# Motorsystem.net
KiCad netlist of a schematic drawn in EAGLE
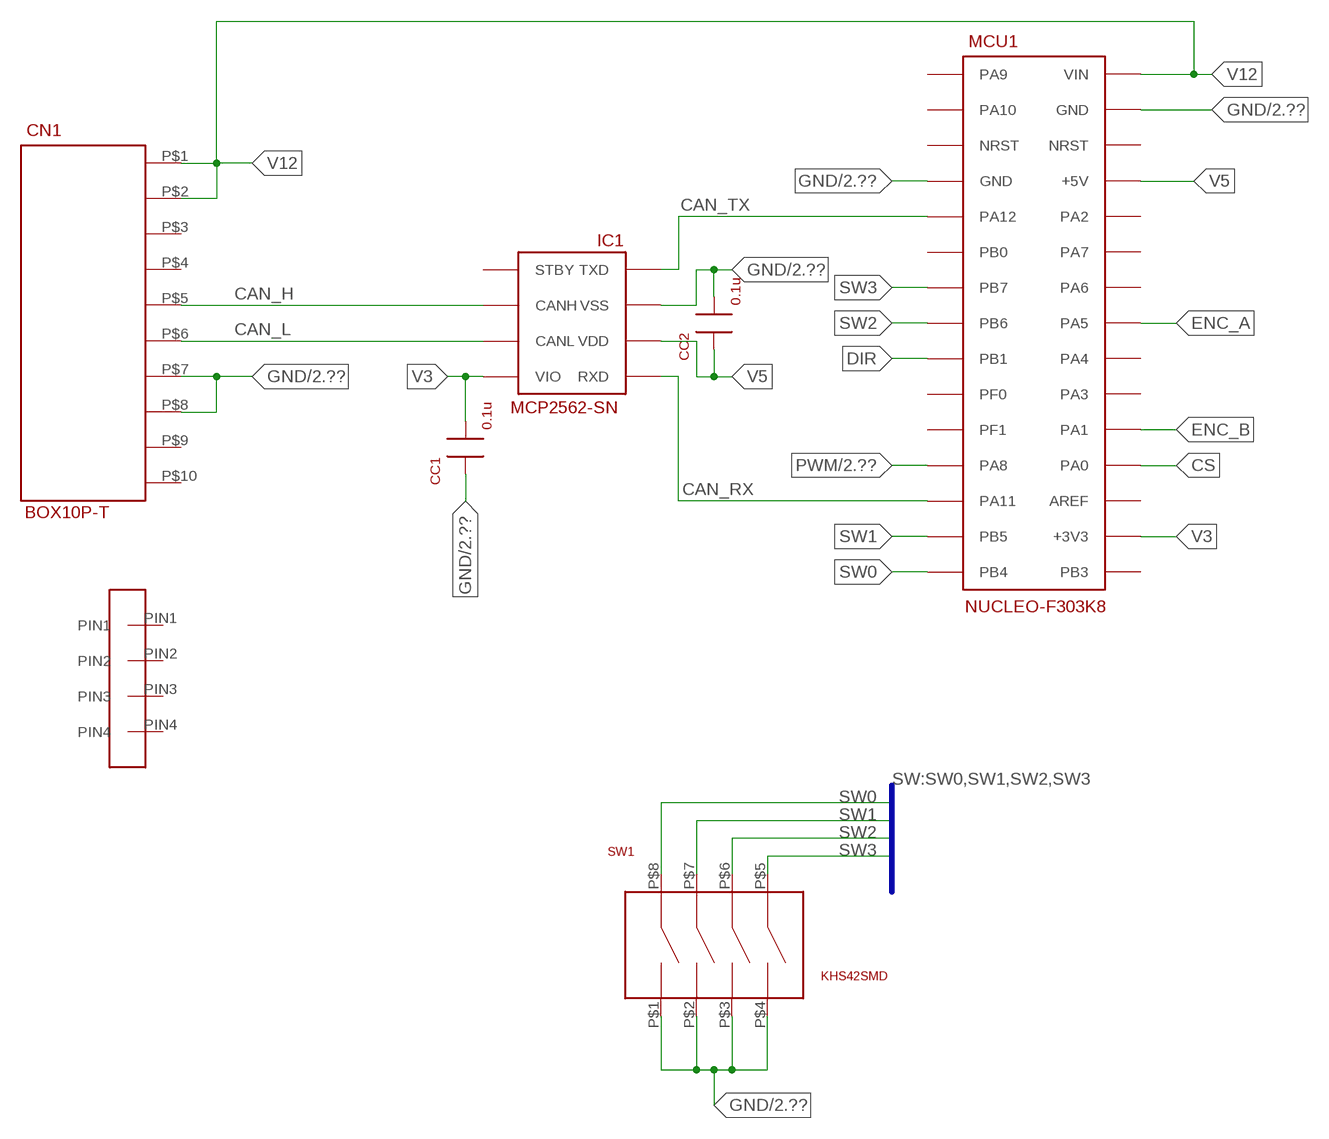
[diagram p0: schematic, sheet 1]
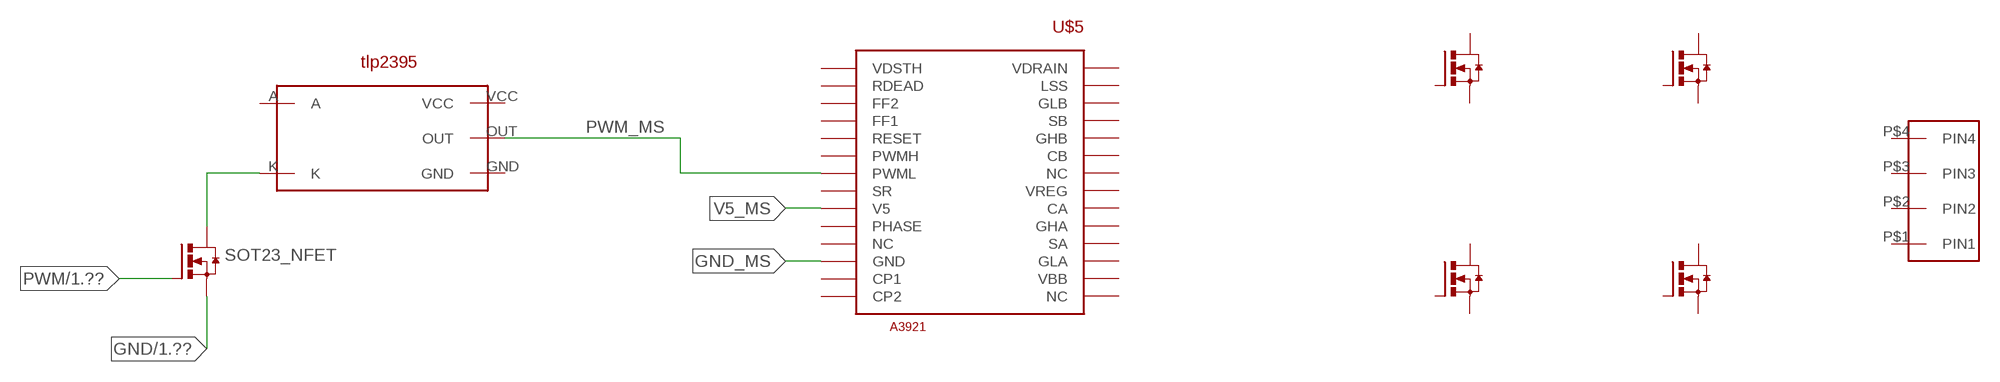
[diagram p1: schematic, sheet 2]

(export (version "E")
  (design (tool "Eeschema 10.0.6"))
  (components
    (comp (ref "CC1")
      (value "0.1u")
      (footprint "eagle-import:C1608")
      (libsource (lib "eagle-import") (part "MLCC1608"))
    )
    (comp (ref "CC2")
      (value "0.1u")
      (footprint "eagle-import:C1608")
      (libsource (lib "eagle-import") (part "MLCC1608"))
    )
    (comp (ref "CN1")
      (value "BOX10P-T")
      (footprint "eagle-import:BOX10P-T")
      (libsource (lib "eagle-import") (part "BOX10P-T"))
    )
    (comp (ref "IC1")
      (value "MCP2562-SN")
      (footprint "eagle-import:SOIC8")
      (libsource (lib "eagle-import") (part "MCP2562-SN"))
    )
    (comp (ref "MCU1")
      (value "NUCLEO-F303K8")
      (footprint "eagle-import:NUCLEO-NANO")
      (libsource (lib "eagle-import") (part "NUCLEO-F303K8"))
    )
    (comp (ref "SW1")
      (value "KHS42SMD")
      (footprint "eagle-import:KHS42")
      (libsource (lib "eagle-import") (part "KHS42SMD"))
    )
    (comp (ref "U$3")
      (value "DF1B_L_4P")
      (footprint "eagle-import:DF1B_L_4P")
      (libsource (lib "eagle-import") (part "DF1B_L_4P"))
    )
    (comp (ref "U$1")
      (value "TLP2395")
      (footprint "eagle-import:TLP2395")
      (libsource (lib "eagle-import") (part "TLP2395"))
    )
    (comp (ref "U$2")
      (value "SOT23_NFET")
      (footprint "eagle-import:SOT23_NFET")
      (libsource (lib "eagle-import") (part "SOT23_NFET"))
    )
    (comp (ref "U$4")
      (value "NP52N06SLG")
      (footprint "eagle-import:NP52N06SLG")
      (libsource (lib "eagle-import") (part "NP52N06SLG"))
    )
    (comp (ref "U$5")
      (value "A3921")
      (footprint "eagle-import:A3921")
      (libsource (lib "eagle-import") (part "A3921"))
    )
    (comp (ref "U$6")
      (value "NP52N06SLG")
      (footprint "eagle-import:NP52N06SLG")
      (libsource (lib "eagle-import") (part "NP52N06SLG"))
    )
    (comp (ref "U$7")
      (value "NP52N06SLG")
      (footprint "eagle-import:NP52N06SLG")
      (libsource (lib "eagle-import") (part "NP52N06SLG"))
    )
    (comp (ref "U$8")
      (value "NP52N06SLG")
      (footprint "eagle-import:NP52N06SLG")
      (libsource (lib "eagle-import") (part "NP52N06SLG"))
    )
    (comp (ref "U$9")
      (value "VL_4P")
      (footprint "eagle-import:VL_4P")
      (libsource (lib "eagle-import") (part "VL_4P"))
    )
  )
  (nets
    (net (code "3") (name "CAN_H") (class "Default")
      (node (ref "CN1") (pin "P$5") (pinfunction "P$5_P$5") (pintype "bidirectional"))
      (node (ref "IC1") (pin "P$7") (pinfunction "CANH_P$7") (pintype "bidirectional"))
    )
    (net (code "4") (name "CAN_L") (class "Default")
      (node (ref "CN1") (pin "P$6") (pinfunction "P$6_P$6") (pintype "bidirectional"))
      (node (ref "IC1") (pin "P$6") (pinfunction "CANL_P$6") (pintype "bidirectional"))
    )
    (net (code "5") (name "CAN_RX") (class "Default")
      (node (ref "IC1") (pin "P$4") (pinfunction "RXD_P$4") (pintype "bidirectional"))
      (node (ref "MCU1") (pin "P$13") (pinfunction "PA11_P$13") (pintype "bidirectional"))
    )
    (net (code "6") (name "CAN_TX") (class "Default")
      (node (ref "IC1") (pin "P$1") (pinfunction "TXD_P$1") (pintype "bidirectional"))
      (node (ref "MCU1") (pin "P$5") (pinfunction "PA12_P$5") (pintype "bidirectional"))
    )
    (net (code "7") (name "CS") (class "Default")
      (node (ref "MCU1") (pin "P$19") (pinfunction "PA0_P$19") (pintype "bidirectional"))
    )
    (net (code "8") (name "DIR") (class "Default")
      (node (ref "MCU1") (pin "P$9") (pinfunction "PB1_P$9") (pintype "bidirectional"))
    )
    (net (code "9") (name "ENC_A") (class "Default")
      (node (ref "MCU1") (pin "P$23") (pinfunction "PA5_P$23") (pintype "bidirectional"))
    )
    (net (code "10") (name "ENC_B") (class "Default")
      (node (ref "MCU1") (pin "P$20") (pinfunction "PA1_P$20") (pintype "bidirectional"))
    )
    (net (code "11") (name "GND") (class "Default")
      (node (ref "CC1") (pin "P$1") (pinfunction "P$1_P$1") (pintype "bidirectional"))
      (node (ref "CC2") (pin "P$2") (pinfunction "P$2_P$2") (pintype "bidirectional"))
      (node (ref "CN1") (pin "P$7") (pinfunction "P$7_P$7") (pintype "bidirectional"))
      (node (ref "CN1") (pin "P$8") (pinfunction "P$8_P$8") (pintype "bidirectional"))
      (node (ref "IC1") (pin "P$2") (pinfunction "VSS_P$2") (pintype "bidirectional"))
      (node (ref "MCU1") (pin "P$29") (pinfunction "GND_P$29") (pintype "bidirectional"))
      (node (ref "MCU1") (pin "P$4") (pinfunction "GND_P$4") (pintype "bidirectional"))
      (node (ref "SW1") (pin "P$1") (pinfunction "P$1_P$1") (pintype "bidirectional"))
      (node (ref "SW1") (pin "P$2") (pinfunction "P$2_P$2") (pintype "bidirectional"))
      (node (ref "SW1") (pin "P$3") (pinfunction "P$3_P$3") (pintype "bidirectional"))
      (node (ref "SW1") (pin "P$4") (pinfunction "P$4_P$4") (pintype "bidirectional"))
      (node (ref "U$2") (pin "PIN2_S") (pinfunction "PIN2_S_PIN2_S") (pintype "passive"))
    )
    (net (code "12") (name "GND_MS") (class "Default")
      (node (ref "U$5") (pin "PAD") (pinfunction "GND_PAD") (pintype "bidirectional"))
      (node (ref "U$5") (pin "PIN17") (pinfunction "GND_PIN17") (pintype "bidirectional"))
    )
    (net (code "13") (name "Net-(U$1-PadK)") (class "Default")
      (node (ref "U$1") (pin "K") (pinfunction "K_K") (pintype "bidirectional"))
      (node (ref "U$2") (pin "PIN3_D") (pinfunction "PIN3_D_PIN3_D") (pintype "passive"))
    )
    (net (code "14") (name "PWM") (class "Default")
      (node (ref "MCU1") (pin "P$12") (pinfunction "PA8_P$12") (pintype "bidirectional"))
      (node (ref "U$2") (pin "PIN1_G") (pinfunction "PIN1_G_PIN1_G") (pintype "passive"))
    )
    (net (code "15") (name "PWM_MS") (class "Default")
      (node (ref "U$1") (pin "OUT") (pinfunction "OUT_OUT") (pintype "bidirectional"))
      (node (ref "U$5") (pin "PIN22") (pinfunction "PWML_PIN22") (pintype "bidirectional"))
    )
    (net (code "16") (name "SW0") (class "Default")
      (node (ref "MCU1") (pin "P$15") (pinfunction "PB4_P$15") (pintype "bidirectional"))
      (node (ref "SW1") (pin "P$8") (pinfunction "P$8_P$8") (pintype "bidirectional"))
    )
    (net (code "17") (name "SW1") (class "Default")
      (node (ref "MCU1") (pin "P$14") (pinfunction "PB5_P$14") (pintype "bidirectional"))
      (node (ref "SW1") (pin "P$7") (pinfunction "P$7_P$7") (pintype "bidirectional"))
    )
    (net (code "18") (name "SW2") (class "Default")
      (node (ref "MCU1") (pin "P$8") (pinfunction "PB6_P$8") (pintype "bidirectional"))
      (node (ref "SW1") (pin "P$6") (pinfunction "P$6_P$6") (pintype "bidirectional"))
    )
    (net (code "19") (name "SW3") (class "Default")
      (node (ref "MCU1") (pin "P$7") (pinfunction "PB7_P$7") (pintype "bidirectional"))
      (node (ref "SW1") (pin "P$5") (pinfunction "P$5_P$5") (pintype "bidirectional"))
    )
    (net (code "20") (name "V3") (class "Default")
      (node (ref "CC1") (pin "P$2") (pinfunction "P$2_P$2") (pintype "bidirectional"))
      (node (ref "IC1") (pin "P$5") (pinfunction "VIO_P$5") (pintype "bidirectional"))
      (node (ref "MCU1") (pin "P$17") (pinfunction "+3V3_P$17") (pintype "bidirectional"))
    )
    (net (code "21") (name "V5") (class "Default")
      (node (ref "CC2") (pin "P$1") (pinfunction "P$1_P$1") (pintype "bidirectional"))
      (node (ref "IC1") (pin "P$3") (pinfunction "VDD_P$3") (pintype "bidirectional"))
      (node (ref "MCU1") (pin "P$27") (pinfunction "+5V_P$27") (pintype "bidirectional"))
    )
    (net (code "22") (name "V5_MS") (class "Default")
      (node (ref "U$5") (pin "PIN20") (pinfunction "V5_PIN20") (pintype "bidirectional"))
    )
    (net (code "23") (name "V12") (class "Default")
      (node (ref "CN1") (pin "P$1") (pinfunction "P$1_P$1") (pintype "bidirectional"))
      (node (ref "CN1") (pin "P$2") (pinfunction "P$2_P$2") (pintype "bidirectional"))
      (node (ref "MCU1") (pin "P$30") (pinfunction "VIN_P$30") (pintype "bidirectional"))
    )
    (net (code "24") (name "unconnected-(CN1-PadP$3)") (class "Default")
      (node (ref "CN1") (pin "P$3") (pinfunction "P$3_P$3") (pintype "bidirectional"))
    )
    (net (code "25") (name "unconnected-(CN1-PadP$4)") (class "Default")
      (node (ref "CN1") (pin "P$4") (pinfunction "P$4_P$4") (pintype "bidirectional"))
    )
    (net (code "26") (name "unconnected-(CN1-PadP$9)") (class "Default")
      (node (ref "CN1") (pin "P$9") (pinfunction "P$9_P$9") (pintype "bidirectional"))
    )
    (net (code "27") (name "unconnected-(CN1-PadP$10)") (class "Default")
      (node (ref "CN1") (pin "P$10") (pinfunction "P$10_P$10") (pintype "bidirectional"))
    )
    (net (code "28") (name "unconnected-(IC1-STBY-PadP$8)") (class "Default")
      (node (ref "IC1") (pin "P$8") (pinfunction "STBY_P$8") (pintype "bidirectional"))
    )
    (net (code "29") (name "unconnected-(MCU1-AREF-PadP$18)") (class "Default")
      (node (ref "MCU1") (pin "P$18") (pinfunction "AREF_P$18") (pintype "bidirectional"))
    )
    (net (code "30") (name "unconnected-(MCU1-NRST-PadP$3)") (class "Default")
      (node (ref "MCU1") (pin "P$3") (pinfunction "NRST_P$3") (pintype "bidirectional"))
    )
    (net (code "31") (name "unconnected-(MCU1-NRST-PadP$28)") (class "Default")
      (node (ref "MCU1") (pin "P$28") (pinfunction "NRST_P$28") (pintype "bidirectional"))
    )
    (net (code "32") (name "unconnected-(MCU1-PA2-PadP$26)") (class "Default")
      (node (ref "MCU1") (pin "P$26") (pinfunction "PA2_P$26") (pintype "bidirectional"))
    )
    (net (code "33") (name "unconnected-(MCU1-PA3-PadP$21)") (class "Default")
      (node (ref "MCU1") (pin "P$21") (pinfunction "PA3_P$21") (pintype "bidirectional"))
    )
    (net (code "34") (name "unconnected-(MCU1-PA4-PadP$22)") (class "Default")
      (node (ref "MCU1") (pin "P$22") (pinfunction "PA4_P$22") (pintype "bidirectional"))
    )
    (net (code "35") (name "unconnected-(MCU1-PA6-PadP$24)") (class "Default")
      (node (ref "MCU1") (pin "P$24") (pinfunction "PA6_P$24") (pintype "bidirectional"))
    )
    (net (code "36") (name "unconnected-(MCU1-PA7-PadP$25)") (class "Default")
      (node (ref "MCU1") (pin "P$25") (pinfunction "PA7_P$25") (pintype "bidirectional"))
    )
    (net (code "37") (name "unconnected-(MCU1-PA9-PadP$1)") (class "Default")
      (node (ref "MCU1") (pin "P$1") (pinfunction "PA9_P$1") (pintype "bidirectional"))
    )
    (net (code "38") (name "unconnected-(MCU1-PA10-PadP$2)") (class "Default")
      (node (ref "MCU1") (pin "P$2") (pinfunction "PA10_P$2") (pintype "bidirectional"))
    )
    (net (code "39") (name "unconnected-(MCU1-PB0-PadP$6)") (class "Default")
      (node (ref "MCU1") (pin "P$6") (pinfunction "PB0_P$6") (pintype "bidirectional"))
    )
    (net (code "40") (name "unconnected-(MCU1-PB3-PadP$16)") (class "Default")
      (node (ref "MCU1") (pin "P$16") (pinfunction "PB3_P$16") (pintype "bidirectional"))
    )
    (net (code "41") (name "unconnected-(MCU1-PF0-PadP$10)") (class "Default")
      (node (ref "MCU1") (pin "P$10") (pinfunction "PF0_P$10") (pintype "bidirectional"))
    )
    (net (code "42") (name "unconnected-(MCU1-PF1-PadP$11)") (class "Default")
      (node (ref "MCU1") (pin "P$11") (pinfunction "PF1_P$11") (pintype "bidirectional"))
    )
    (net (code "43") (name "unconnected-(U$1-PadA)") (class "Default")
      (node (ref "U$1") (pin "A") (pinfunction "A_A") (pintype "bidirectional"))
    )
    (net (code "44") (name "unconnected-(U$1-PadGND)") (class "Default")
      (node (ref "U$1") (pin "GND") (pinfunction "GND_GND") (pintype "bidirectional"))
    )
    (net (code "45") (name "unconnected-(U$1-PadVCC)") (class "Default")
      (node (ref "U$1") (pin "VCC") (pinfunction "VCC_VCC") (pintype "bidirectional"))
    )
    (net (code "46") (name "unconnected-(U$3-PadPIN1)") (class "Default")
      (node (ref "U$3") (pin "PIN1") (pinfunction "PIN1_PIN1") (pintype "bidirectional"))
    )
    (net (code "47") (name "unconnected-(U$3-PadPIN2)") (class "Default")
      (node (ref "U$3") (pin "PIN2") (pinfunction "PIN2_PIN2") (pintype "bidirectional"))
    )
    (net (code "48") (name "unconnected-(U$3-PadPIN3)") (class "Default")
      (node (ref "U$3") (pin "PIN3") (pinfunction "PIN3_PIN3") (pintype "bidirectional"))
    )
    (net (code "49") (name "unconnected-(U$3-PadPIN4)") (class "Default")
      (node (ref "U$3") (pin "PIN4") (pinfunction "PIN4_PIN4") (pintype "bidirectional"))
    )
    (net (code "50") (name "unconnected-(U$4-PadPIN1_G)") (class "Default")
      (node (ref "U$4") (pin "PIN1_G") (pinfunction "PIN1_G_PIN1_G") (pintype "passive"))
    )
    (net (code "51") (name "unconnected-(U$4-PadPIN2_D)") (class "Default")
      (node (ref "U$4") (pin "PIN2_D") (pinfunction "PIN2_D_PIN2_D") (pintype "passive"))
    )
    (net (code "52") (name "unconnected-(U$4-PadPIN3_S)") (class "Default")
      (node (ref "U$4") (pin "PIN3_S") (pinfunction "PIN3_S_PIN3_S") (pintype "passive"))
    )
    (net (code "53") (name "unconnected-(U$5-CA-PadPIN9)") (class "Default")
      (node (ref "U$5") (pin "PIN9") (pinfunction "CA_PIN9") (pintype "bidirectional"))
    )
    (net (code "54") (name "unconnected-(U$5-CB-PadPIN6)") (class "Default")
      (node (ref "U$5") (pin "PIN6") (pinfunction "CB_PIN6") (pintype "bidirectional"))
    )
    (net (code "55") (name "unconnected-(U$5-CP1-PadPIN16)") (class "Default")
      (node (ref "U$5") (pin "PIN16") (pinfunction "CP1_PIN16") (pintype "bidirectional"))
    )
    (net (code "56") (name "unconnected-(U$5-CP2-PadPIN15)") (class "Default")
      (node (ref "U$5") (pin "PIN15") (pinfunction "CP2_PIN15") (pintype "bidirectional"))
    )
    (net (code "57") (name "unconnected-(U$5-FF1-PadPIN25)") (class "Default")
      (node (ref "U$5") (pin "PIN25") (pinfunction "FF1_PIN25") (pintype "bidirectional"))
    )
    (net (code "58") (name "unconnected-(U$5-FF2-PadPIN26)") (class "Default")
      (node (ref "U$5") (pin "PIN26") (pinfunction "FF2_PIN26") (pintype "bidirectional"))
    )
    (net (code "59") (name "unconnected-(U$5-GHA-PadPIN10)") (class "Default")
      (node (ref "U$5") (pin "PIN10") (pinfunction "GHA_PIN10") (pintype "bidirectional"))
    )
    (net (code "60") (name "unconnected-(U$5-GHB-PadPIN5)") (class "Default")
      (node (ref "U$5") (pin "PIN5") (pinfunction "GHB_PIN5") (pintype "bidirectional"))
    )
    (net (code "61") (name "unconnected-(U$5-GLA-PadPIN12)") (class "Default")
      (node (ref "U$5") (pin "PIN12") (pinfunction "GLA_PIN12") (pintype "bidirectional"))
    )
    (net (code "62") (name "unconnected-(U$5-GLB-PadPIN3)") (class "Default")
      (node (ref "U$5") (pin "PIN3") (pinfunction "GLB_PIN3") (pintype "bidirectional"))
    )
    (net (code "63") (name "unconnected-(U$5-LSS-PadPIN2)") (class "Default")
      (node (ref "U$5") (pin "PIN2") (pinfunction "LSS_PIN2") (pintype "bidirectional"))
    )
    (net (code "64") (name "unconnected-(U$5-NC-PadPIN7)") (class "Default")
      (node (ref "U$5") (pin "PIN7") (pinfunction "NC_PIN7") (pintype "no_connect"))
    )
    (net (code "65") (name "unconnected-(U$5-NC-PadPIN14)") (class "Default")
      (node (ref "U$5") (pin "PIN14") (pinfunction "NC_PIN14") (pintype "no_connect"))
    )
    (net (code "66") (name "unconnected-(U$5-NC-PadPIN18)") (class "Default")
      (node (ref "U$5") (pin "PIN18") (pinfunction "NC_PIN18") (pintype "no_connect"))
    )
    (net (code "67") (name "unconnected-(U$5-PHASE-PadPIN19)") (class "Default")
      (node (ref "U$5") (pin "PIN19") (pinfunction "PHASE_PIN19") (pintype "bidirectional"))
    )
    (net (code "68") (name "unconnected-(U$5-PWMH-PadPIN23)") (class "Default")
      (node (ref "U$5") (pin "PIN23") (pinfunction "PWMH_PIN23") (pintype "bidirectional"))
    )
    (net (code "69") (name "unconnected-(U$5-RDEAD-PadPIN27)") (class "Default")
      (node (ref "U$5") (pin "PIN27") (pinfunction "RDEAD_PIN27") (pintype "bidirectional"))
    )
    (net (code "70") (name "unconnected-(U$5-RESET-PadPIN24)") (class "Default")
      (node (ref "U$5") (pin "PIN24") (pinfunction "RESET_PIN24") (pintype "bidirectional"))
    )
    (net (code "71") (name "unconnected-(U$5-SA-PadPIN11)") (class "Default")
      (node (ref "U$5") (pin "PIN11") (pinfunction "SA_PIN11") (pintype "bidirectional"))
    )
    (net (code "72") (name "unconnected-(U$5-SB-PadPIN4)") (class "Default")
      (node (ref "U$5") (pin "PIN4") (pinfunction "SB_PIN4") (pintype "bidirectional"))
    )
    (net (code "73") (name "unconnected-(U$5-SR-PadPIN21)") (class "Default")
      (node (ref "U$5") (pin "PIN21") (pinfunction "SR_PIN21") (pintype "bidirectional"))
    )
    (net (code "74") (name "unconnected-(U$5-VBB-PadPIN13)") (class "Default")
      (node (ref "U$5") (pin "PIN13") (pinfunction "VBB_PIN13") (pintype "bidirectional"))
    )
    (net (code "75") (name "unconnected-(U$5-VDRAIN-PadPIN1)") (class "Default")
      (node (ref "U$5") (pin "PIN1") (pinfunction "VDRAIN_PIN1") (pintype "bidirectional"))
    )
    (net (code "76") (name "unconnected-(U$5-VDSTH-PadPIN28)") (class "Default")
      (node (ref "U$5") (pin "PIN28") (pinfunction "VDSTH_PIN28") (pintype "bidirectional"))
    )
    (net (code "77") (name "unconnected-(U$5-VREG-PadPIN8)") (class "Default")
      (node (ref "U$5") (pin "PIN8") (pinfunction "VREG_PIN8") (pintype "bidirectional"))
    )
    (net (code "78") (name "unconnected-(U$6-PadPIN1_G)") (class "Default")
      (node (ref "U$6") (pin "PIN1_G") (pinfunction "PIN1_G_PIN1_G") (pintype "passive"))
    )
    (net (code "79") (name "unconnected-(U$6-PadPIN2_D)") (class "Default")
      (node (ref "U$6") (pin "PIN2_D") (pinfunction "PIN2_D_PIN2_D") (pintype "passive"))
    )
    (net (code "80") (name "unconnected-(U$6-PadPIN3_S)") (class "Default")
      (node (ref "U$6") (pin "PIN3_S") (pinfunction "PIN3_S_PIN3_S") (pintype "passive"))
    )
    (net (code "81") (name "unconnected-(U$7-PadPIN1_G)") (class "Default")
      (node (ref "U$7") (pin "PIN1_G") (pinfunction "PIN1_G_PIN1_G") (pintype "passive"))
    )
    (net (code "82") (name "unconnected-(U$7-PadPIN2_D)") (class "Default")
      (node (ref "U$7") (pin "PIN2_D") (pinfunction "PIN2_D_PIN2_D") (pintype "passive"))
    )
    (net (code "83") (name "unconnected-(U$7-PadPIN3_S)") (class "Default")
      (node (ref "U$7") (pin "PIN3_S") (pinfunction "PIN3_S_PIN3_S") (pintype "passive"))
    )
    (net (code "84") (name "unconnected-(U$8-PadPIN1_G)") (class "Default")
      (node (ref "U$8") (pin "PIN1_G") (pinfunction "PIN1_G_PIN1_G") (pintype "passive"))
    )
    (net (code "85") (name "unconnected-(U$8-PadPIN2_D)") (class "Default")
      (node (ref "U$8") (pin "PIN2_D") (pinfunction "PIN2_D_PIN2_D") (pintype "passive"))
    )
    (net (code "86") (name "unconnected-(U$8-PadPIN3_S)") (class "Default")
      (node (ref "U$8") (pin "PIN3_S") (pinfunction "PIN3_S_PIN3_S") (pintype "passive"))
    )
    (net (code "87") (name "unconnected-(U$9-PIN1-PadP$1)") (class "Default")
      (node (ref "U$9") (pin "P$1") (pinfunction "PIN1_P$1") (pintype "bidirectional"))
    )
    (net (code "88") (name "unconnected-(U$9-PIN2-PadP$2)") (class "Default")
      (node (ref "U$9") (pin "P$2") (pinfunction "PIN2_P$2") (pintype "bidirectional"))
    )
    (net (code "89") (name "unconnected-(U$9-PIN3-PadP$3)") (class "Default")
      (node (ref "U$9") (pin "P$3") (pinfunction "PIN3_P$3") (pintype "bidirectional"))
    )
    (net (code "90") (name "unconnected-(U$9-PIN4-PadP$4)") (class "Default")
      (node (ref "U$9") (pin "P$4") (pinfunction "PIN4_P$4") (pintype "bidirectional"))
    )
  )
)
